# conector_santec.net
KiCad netlist of a schematic drawn in EAGLE
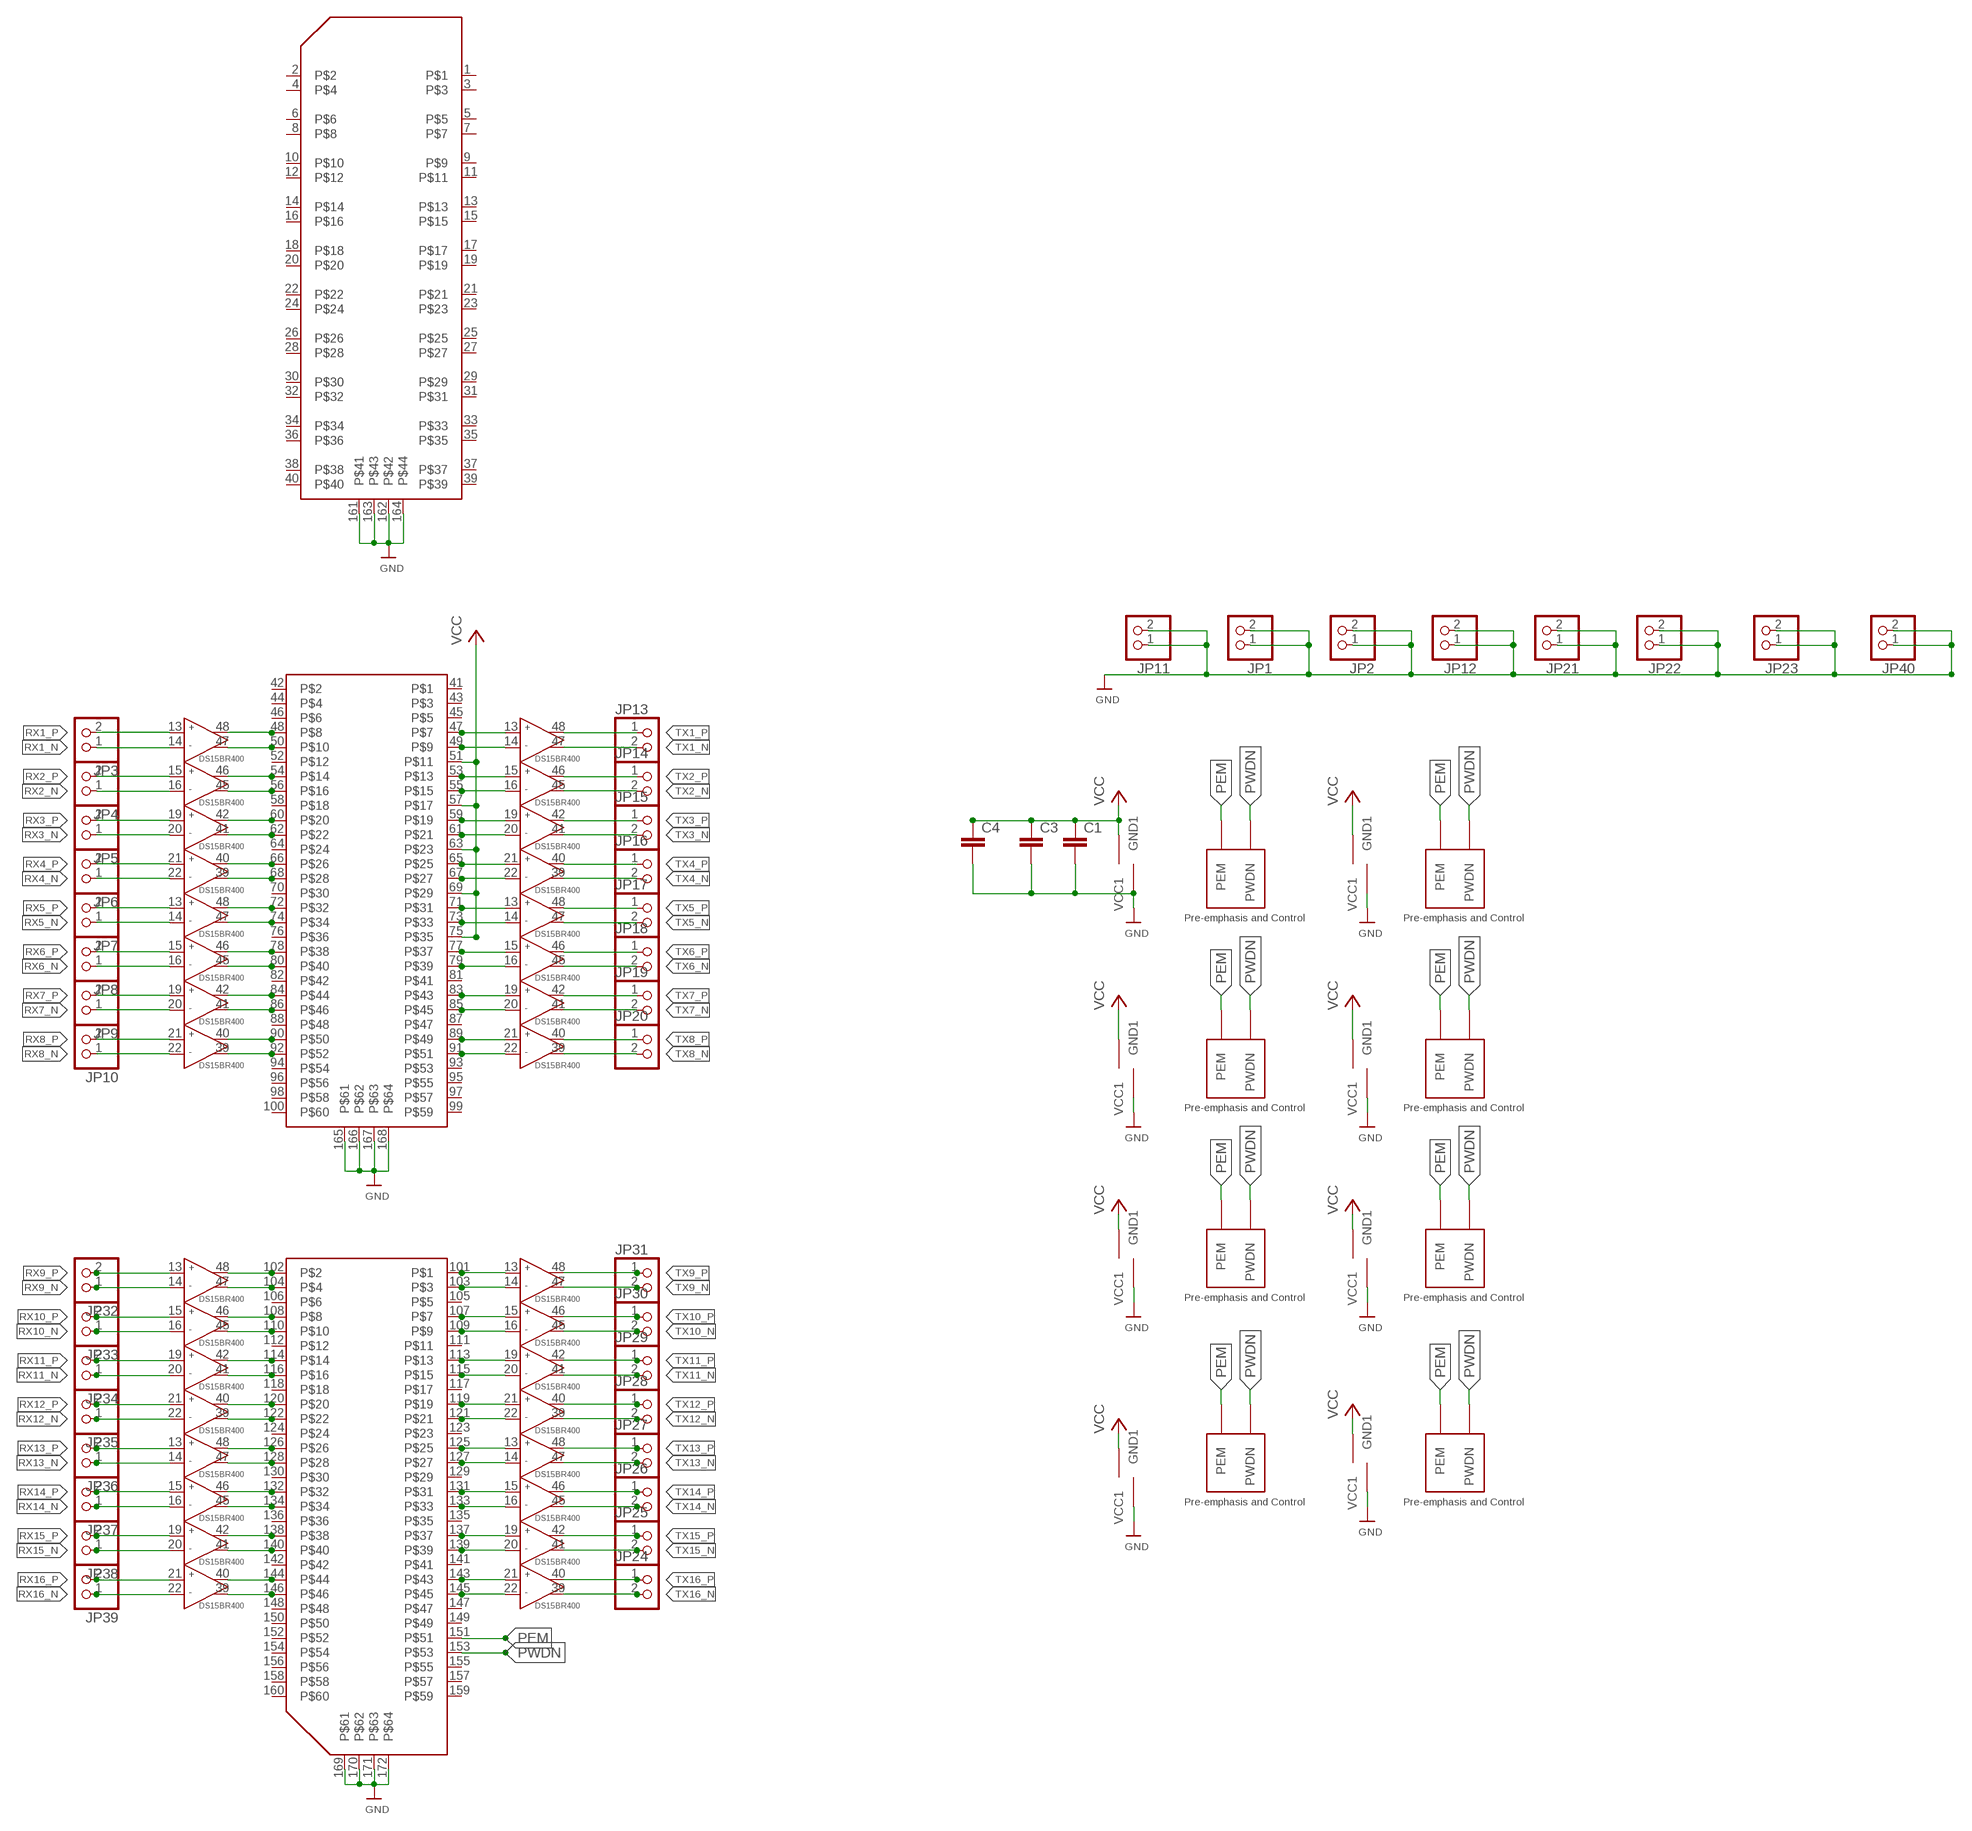
[diagram p0: schematic, sheet 1]

(export (version "E")
  (design (tool "Eeschema 10.0.6"))
  (components
    (comp (ref "C1")
      (value "C-EUC0603")
      (footprint "eagle-import:C0603")
      (libsource (lib "eagle-import") (part "C-EUC0603"))
    )
    (comp (ref "C3")
      (value "C-EUC0603")
      (footprint "eagle-import:C0603")
      (libsource (lib "eagle-import") (part "C-EUC0603"))
    )
    (comp (ref "C4")
      (value "C-EUC0603")
      (footprint "eagle-import:C0603")
      (libsource (lib "eagle-import") (part "C-EUC0603"))
    )
    (comp (ref "JP1")
      (value "HEADER-1X2ROUND")
      (footprint "eagle-import:1X02_ROUND")
      (libsource (lib "eagle-import") (part "HEADER-1X2ROUND"))
    )
    (comp (ref "JP2")
      (value "HEADER-1X2ROUND")
      (footprint "eagle-import:1X02_ROUND")
      (libsource (lib "eagle-import") (part "HEADER-1X2ROUND"))
    )
    (comp (ref "JP3")
      (value "HEADER-1X2ROUND")
      (footprint "eagle-import:1X02_ROUND")
      (libsource (lib "eagle-import") (part "HEADER-1X2ROUND"))
    )
    (comp (ref "JP4")
      (value "HEADER-1X2ROUND")
      (footprint "eagle-import:1X02_ROUND")
      (libsource (lib "eagle-import") (part "HEADER-1X2ROUND"))
    )
    (comp (ref "JP5")
      (value "HEADER-1X2ROUND")
      (footprint "eagle-import:1X02_ROUND")
      (libsource (lib "eagle-import") (part "HEADER-1X2ROUND"))
    )
    (comp (ref "JP6")
      (value "HEADER-1X2ROUND")
      (footprint "eagle-import:1X02_ROUND")
      (libsource (lib "eagle-import") (part "HEADER-1X2ROUND"))
    )
    (comp (ref "JP7")
      (value "HEADER-1X2ROUND")
      (footprint "eagle-import:1X02_ROUND")
      (libsource (lib "eagle-import") (part "HEADER-1X2ROUND"))
    )
    (comp (ref "JP8")
      (value "HEADER-1X2ROUND")
      (footprint "eagle-import:1X02_ROUND")
      (libsource (lib "eagle-import") (part "HEADER-1X2ROUND"))
    )
    (comp (ref "JP9")
      (value "HEADER-1X2ROUND")
      (footprint "eagle-import:1X02_ROUND")
      (libsource (lib "eagle-import") (part "HEADER-1X2ROUND"))
    )
    (comp (ref "JP10")
      (value "HEADER-1X2ROUND")
      (footprint "eagle-import:1X02_ROUND")
      (libsource (lib "eagle-import") (part "HEADER-1X2ROUND"))
    )
    (comp (ref "JP11")
      (value "HEADER-1X2ROUND")
      (footprint "eagle-import:1X02_ROUND")
      (libsource (lib "eagle-import") (part "HEADER-1X2ROUND"))
    )
    (comp (ref "JP12")
      (value "HEADER-1X2ROUND")
      (footprint "eagle-import:1X02_ROUND")
      (libsource (lib "eagle-import") (part "HEADER-1X2ROUND"))
    )
    (comp (ref "JP13")
      (value "HEADER-1X2ROUND")
      (footprint "eagle-import:1X02_ROUND")
      (libsource (lib "eagle-import") (part "HEADER-1X2ROUND"))
    )
    (comp (ref "JP14")
      (value "HEADER-1X2ROUND")
      (footprint "eagle-import:1X02_ROUND")
      (libsource (lib "eagle-import") (part "HEADER-1X2ROUND"))
    )
    (comp (ref "JP15")
      (value "HEADER-1X2ROUND")
      (footprint "eagle-import:1X02_ROUND")
      (libsource (lib "eagle-import") (part "HEADER-1X2ROUND"))
    )
    (comp (ref "JP16")
      (value "HEADER-1X2ROUND")
      (footprint "eagle-import:1X02_ROUND")
      (libsource (lib "eagle-import") (part "HEADER-1X2ROUND"))
    )
    (comp (ref "JP17")
      (value "HEADER-1X2ROUND")
      (footprint "eagle-import:1X02_ROUND")
      (libsource (lib "eagle-import") (part "HEADER-1X2ROUND"))
    )
    (comp (ref "JP18")
      (value "HEADER-1X2ROUND")
      (footprint "eagle-import:1X02_ROUND")
      (libsource (lib "eagle-import") (part "HEADER-1X2ROUND"))
    )
    (comp (ref "JP19")
      (value "HEADER-1X2ROUND")
      (footprint "eagle-import:1X02_ROUND")
      (libsource (lib "eagle-import") (part "HEADER-1X2ROUND"))
    )
    (comp (ref "JP20")
      (value "HEADER-1X2ROUND")
      (footprint "eagle-import:1X02_ROUND")
      (libsource (lib "eagle-import") (part "HEADER-1X2ROUND"))
    )
    (comp (ref "JP21")
      (value "HEADER-1X2ROUND")
      (footprint "eagle-import:1X02_ROUND")
      (libsource (lib "eagle-import") (part "HEADER-1X2ROUND"))
    )
    (comp (ref "JP22")
      (value "HEADER-1X2ROUND")
      (footprint "eagle-import:1X02_ROUND")
      (libsource (lib "eagle-import") (part "HEADER-1X2ROUND"))
    )
    (comp (ref "JP23")
      (value "HEADER-1X2ROUND")
      (footprint "eagle-import:1X02_ROUND")
      (libsource (lib "eagle-import") (part "HEADER-1X2ROUND"))
    )
    (comp (ref "JP24")
      (value "HEADER-1X2ROUND")
      (footprint "eagle-import:1X02_ROUND")
      (libsource (lib "eagle-import") (part "HEADER-1X2ROUND"))
    )
    (comp (ref "JP25")
      (value "HEADER-1X2ROUND")
      (footprint "eagle-import:1X02_ROUND")
      (libsource (lib "eagle-import") (part "HEADER-1X2ROUND"))
    )
    (comp (ref "JP26")
      (value "HEADER-1X2ROUND")
      (footprint "eagle-import:1X02_ROUND")
      (libsource (lib "eagle-import") (part "HEADER-1X2ROUND"))
    )
    (comp (ref "JP27")
      (value "HEADER-1X2ROUND")
      (footprint "eagle-import:1X02_ROUND")
      (libsource (lib "eagle-import") (part "HEADER-1X2ROUND"))
    )
    (comp (ref "JP28")
      (value "HEADER-1X2ROUND")
      (footprint "eagle-import:1X02_ROUND")
      (libsource (lib "eagle-import") (part "HEADER-1X2ROUND"))
    )
    (comp (ref "JP29")
      (value "HEADER-1X2ROUND")
      (footprint "eagle-import:1X02_ROUND")
      (libsource (lib "eagle-import") (part "HEADER-1X2ROUND"))
    )
    (comp (ref "JP30")
      (value "HEADER-1X2ROUND")
      (footprint "eagle-import:1X02_ROUND")
      (libsource (lib "eagle-import") (part "HEADER-1X2ROUND"))
    )
    (comp (ref "JP31")
      (value "HEADER-1X2ROUND")
      (footprint "eagle-import:1X02_ROUND")
      (libsource (lib "eagle-import") (part "HEADER-1X2ROUND"))
    )
    (comp (ref "JP32")
      (value "HEADER-1X2ROUND")
      (footprint "eagle-import:1X02_ROUND")
      (libsource (lib "eagle-import") (part "HEADER-1X2ROUND"))
    )
    (comp (ref "JP33")
      (value "HEADER-1X2ROUND")
      (footprint "eagle-import:1X02_ROUND")
      (libsource (lib "eagle-import") (part "HEADER-1X2ROUND"))
    )
    (comp (ref "JP34")
      (value "HEADER-1X2ROUND")
      (footprint "eagle-import:1X02_ROUND")
      (libsource (lib "eagle-import") (part "HEADER-1X2ROUND"))
    )
    (comp (ref "JP35")
      (value "HEADER-1X2ROUND")
      (footprint "eagle-import:1X02_ROUND")
      (libsource (lib "eagle-import") (part "HEADER-1X2ROUND"))
    )
    (comp (ref "JP36")
      (value "HEADER-1X2ROUND")
      (footprint "eagle-import:1X02_ROUND")
      (libsource (lib "eagle-import") (part "HEADER-1X2ROUND"))
    )
    (comp (ref "JP37")
      (value "HEADER-1X2ROUND")
      (footprint "eagle-import:1X02_ROUND")
      (libsource (lib "eagle-import") (part "HEADER-1X2ROUND"))
    )
    (comp (ref "JP38")
      (value "HEADER-1X2ROUND")
      (footprint "eagle-import:1X02_ROUND")
      (libsource (lib "eagle-import") (part "HEADER-1X2ROUND"))
    )
    (comp (ref "JP39")
      (value "HEADER-1X2ROUND")
      (footprint "eagle-import:1X02_ROUND")
      (libsource (lib "eagle-import") (part "HEADER-1X2ROUND"))
    )
    (comp (ref "JP40")
      (value "HEADER-1X2ROUND")
      (footprint "eagle-import:1X02_ROUND")
      (libsource (lib "eagle-import") (part "HEADER-1X2ROUND"))
    )
    (comp (ref "U$1")
      (value "SAMTEC_ASP-122952-01")
      (footprint "eagle-import:ASP-122952-01")
      (libsource (lib "eagle-import") (part "SAMTEC_ASP-122952-01"))
    )
    (comp (ref "U$4")
      (value "DS15BR400")
      (footprint "eagle-import:TQFP48")
      (libsource (lib "eagle-import") (part "DS15BR400"))
    )
    (comp (ref "U$6")
      (value "DS15BR400")
      (footprint "eagle-import:TQFP48")
      (libsource (lib "eagle-import") (part "DS15BR400"))
    )
    (comp (ref "U$7")
      (value "DS15BR400")
      (footprint "eagle-import:TQFP48")
      (libsource (lib "eagle-import") (part "DS15BR400"))
    )
    (comp (ref "U$8")
      (value "DS15BR400")
      (footprint "eagle-import:TQFP48")
      (libsource (lib "eagle-import") (part "DS15BR400"))
    )
    (comp (ref "U$15")
      (value "DS15BR400")
      (footprint "eagle-import:TQFP48")
      (libsource (lib "eagle-import") (part "DS15BR400"))
    )
    (comp (ref "U$16")
      (value "DS15BR400")
      (footprint "eagle-import:TQFP48")
      (libsource (lib "eagle-import") (part "DS15BR400"))
    )
    (comp (ref "U$17")
      (value "DS15BR400")
      (footprint "eagle-import:TQFP48")
      (libsource (lib "eagle-import") (part "DS15BR400"))
    )
    (comp (ref "U$18")
      (value "DS15BR400")
      (footprint "eagle-import:TQFP48")
      (libsource (lib "eagle-import") (part "DS15BR400"))
    )
  )
  (nets
    (net (code "1") (name "GND") (class "Default")
      (node (ref "C1") (pin "2") (pinfunction "2_2") (pintype "passive"))
      (node (ref "C3") (pin "2") (pinfunction "2_2") (pintype "passive"))
      (node (ref "C4") (pin "2") (pinfunction "2_2") (pintype "passive"))
      (node (ref "JP1") (pin "1") (pinfunction "1_1") (pintype "passive"))
      (node (ref "JP1") (pin "2") (pinfunction "2_2") (pintype "passive"))
      (node (ref "JP11") (pin "1") (pinfunction "1_1") (pintype "passive"))
      (node (ref "JP11") (pin "2") (pinfunction "2_2") (pintype "passive"))
      (node (ref "JP12") (pin "1") (pinfunction "1_1") (pintype "passive"))
      (node (ref "JP12") (pin "2") (pinfunction "2_2") (pintype "passive"))
      (node (ref "JP2") (pin "1") (pinfunction "1_1") (pintype "passive"))
      (node (ref "JP2") (pin "2") (pinfunction "2_2") (pintype "passive"))
      (node (ref "JP21") (pin "1") (pinfunction "1_1") (pintype "passive"))
      (node (ref "JP21") (pin "2") (pinfunction "2_2") (pintype "passive"))
      (node (ref "JP22") (pin "1") (pinfunction "1_1") (pintype "passive"))
      (node (ref "JP22") (pin "2") (pinfunction "2_2") (pintype "passive"))
      (node (ref "JP23") (pin "1") (pinfunction "1_1") (pintype "passive"))
      (node (ref "JP23") (pin "2") (pinfunction "2_2") (pintype "passive"))
      (node (ref "JP40") (pin "1") (pinfunction "1_1") (pintype "passive"))
      (node (ref "JP40") (pin "2") (pinfunction "2_2") (pintype "passive"))
      (node (ref "U$1") (pin "161") (pinfunction "P$41_161") (pintype "bidirectional"))
      (node (ref "U$1") (pin "162") (pinfunction "P$42_162") (pintype "bidirectional"))
      (node (ref "U$1") (pin "163") (pinfunction "P$43_163") (pintype "bidirectional"))
      (node (ref "U$1") (pin "164") (pinfunction "P$44_164") (pintype "bidirectional"))
      (node (ref "U$1") (pin "165") (pinfunction "P$61_165") (pintype "bidirectional"))
      (node (ref "U$1") (pin "166") (pinfunction "P$62_166") (pintype "bidirectional"))
      (node (ref "U$1") (pin "167") (pinfunction "P$63_167") (pintype "bidirectional"))
      (node (ref "U$1") (pin "168") (pinfunction "P$64_168") (pintype "bidirectional"))
      (node (ref "U$1") (pin "169") (pinfunction "P$61_169") (pintype "bidirectional"))
      (node (ref "U$1") (pin "170") (pinfunction "P$62_170") (pintype "bidirectional"))
      (node (ref "U$1") (pin "171") (pinfunction "P$63_171") (pintype "bidirectional"))
      (node (ref "U$1") (pin "172") (pinfunction "P$64_172") (pintype "bidirectional"))
      (node (ref "U$15") (pin "17") (pinfunction "GND1_17") (pintype "bidirectional"))
      (node (ref "U$15") (pin "18") (pinfunction "GND1_18") (pintype "bidirectional"))
      (node (ref "U$15") (pin "23") (pinfunction "GND1_23") (pintype "bidirectional"))
      (node (ref "U$15") (pin "24") (pinfunction "GND1_24") (pintype "bidirectional"))
      (node (ref "U$15") (pin "37") (pinfunction "GND1_37") (pintype "bidirectional"))
      (node (ref "U$15") (pin "38") (pinfunction "GND1_38") (pintype "bidirectional"))
      (node (ref "U$15") (pin "43") (pinfunction "GND1_43") (pintype "bidirectional"))
      (node (ref "U$15") (pin "44") (pinfunction "GND1_44") (pintype "bidirectional"))
      (node (ref "U$15") (pin "8") (pinfunction "GND1_8") (pintype "bidirectional"))
      (node (ref "U$15") (pin "9") (pinfunction "GND1_9") (pintype "bidirectional"))
      (node (ref "U$16") (pin "17") (pinfunction "GND1_17") (pintype "bidirectional"))
      (node (ref "U$16") (pin "18") (pinfunction "GND1_18") (pintype "bidirectional"))
      (node (ref "U$16") (pin "23") (pinfunction "GND1_23") (pintype "bidirectional"))
      (node (ref "U$16") (pin "24") (pinfunction "GND1_24") (pintype "bidirectional"))
      (node (ref "U$16") (pin "37") (pinfunction "GND1_37") (pintype "bidirectional"))
      (node (ref "U$16") (pin "38") (pinfunction "GND1_38") (pintype "bidirectional"))
      (node (ref "U$16") (pin "43") (pinfunction "GND1_43") (pintype "bidirectional"))
      (node (ref "U$16") (pin "44") (pinfunction "GND1_44") (pintype "bidirectional"))
      (node (ref "U$16") (pin "8") (pinfunction "GND1_8") (pintype "bidirectional"))
      (node (ref "U$16") (pin "9") (pinfunction "GND1_9") (pintype "bidirectional"))
      (node (ref "U$17") (pin "17") (pinfunction "GND1_17") (pintype "bidirectional"))
      (node (ref "U$17") (pin "18") (pinfunction "GND1_18") (pintype "bidirectional"))
      (node (ref "U$17") (pin "23") (pinfunction "GND1_23") (pintype "bidirectional"))
      (node (ref "U$17") (pin "24") (pinfunction "GND1_24") (pintype "bidirectional"))
      (node (ref "U$17") (pin "37") (pinfunction "GND1_37") (pintype "bidirectional"))
      (node (ref "U$17") (pin "38") (pinfunction "GND1_38") (pintype "bidirectional"))
      (node (ref "U$17") (pin "43") (pinfunction "GND1_43") (pintype "bidirectional"))
      (node (ref "U$17") (pin "44") (pinfunction "GND1_44") (pintype "bidirectional"))
      (node (ref "U$17") (pin "8") (pinfunction "GND1_8") (pintype "bidirectional"))
      (node (ref "U$17") (pin "9") (pinfunction "GND1_9") (pintype "bidirectional"))
      (node (ref "U$18") (pin "17") (pinfunction "GND1_17") (pintype "bidirectional"))
      (node (ref "U$18") (pin "18") (pinfunction "GND1_18") (pintype "bidirectional"))
      (node (ref "U$18") (pin "23") (pinfunction "GND1_23") (pintype "bidirectional"))
      (node (ref "U$18") (pin "24") (pinfunction "GND1_24") (pintype "bidirectional"))
      (node (ref "U$18") (pin "37") (pinfunction "GND1_37") (pintype "bidirectional"))
      (node (ref "U$18") (pin "38") (pinfunction "GND1_38") (pintype "bidirectional"))
      (node (ref "U$18") (pin "43") (pinfunction "GND1_43") (pintype "bidirectional"))
      (node (ref "U$18") (pin "44") (pinfunction "GND1_44") (pintype "bidirectional"))
      (node (ref "U$18") (pin "8") (pinfunction "GND1_8") (pintype "bidirectional"))
      (node (ref "U$18") (pin "9") (pinfunction "GND1_9") (pintype "bidirectional"))
      (node (ref "U$4") (pin "17") (pinfunction "GND1_17") (pintype "bidirectional"))
      (node (ref "U$4") (pin "18") (pinfunction "GND1_18") (pintype "bidirectional"))
      (node (ref "U$4") (pin "23") (pinfunction "GND1_23") (pintype "bidirectional"))
      (node (ref "U$4") (pin "24") (pinfunction "GND1_24") (pintype "bidirectional"))
      (node (ref "U$4") (pin "37") (pinfunction "GND1_37") (pintype "bidirectional"))
      (node (ref "U$4") (pin "38") (pinfunction "GND1_38") (pintype "bidirectional"))
      (node (ref "U$4") (pin "43") (pinfunction "GND1_43") (pintype "bidirectional"))
      (node (ref "U$4") (pin "44") (pinfunction "GND1_44") (pintype "bidirectional"))
      (node (ref "U$4") (pin "8") (pinfunction "GND1_8") (pintype "bidirectional"))
      (node (ref "U$4") (pin "9") (pinfunction "GND1_9") (pintype "bidirectional"))
      (node (ref "U$6") (pin "17") (pinfunction "GND1_17") (pintype "bidirectional"))
      (node (ref "U$6") (pin "18") (pinfunction "GND1_18") (pintype "bidirectional"))
      (node (ref "U$6") (pin "23") (pinfunction "GND1_23") (pintype "bidirectional"))
      (node (ref "U$6") (pin "24") (pinfunction "GND1_24") (pintype "bidirectional"))
      (node (ref "U$6") (pin "37") (pinfunction "GND1_37") (pintype "bidirectional"))
      (node (ref "U$6") (pin "38") (pinfunction "GND1_38") (pintype "bidirectional"))
      (node (ref "U$6") (pin "43") (pinfunction "GND1_43") (pintype "bidirectional"))
      (node (ref "U$6") (pin "44") (pinfunction "GND1_44") (pintype "bidirectional"))
      (node (ref "U$6") (pin "8") (pinfunction "GND1_8") (pintype "bidirectional"))
      (node (ref "U$6") (pin "9") (pinfunction "GND1_9") (pintype "bidirectional"))
      (node (ref "U$7") (pin "17") (pinfunction "GND1_17") (pintype "bidirectional"))
      (node (ref "U$7") (pin "18") (pinfunction "GND1_18") (pintype "bidirectional"))
      (node (ref "U$7") (pin "23") (pinfunction "GND1_23") (pintype "bidirectional"))
      (node (ref "U$7") (pin "24") (pinfunction "GND1_24") (pintype "bidirectional"))
      (node (ref "U$7") (pin "37") (pinfunction "GND1_37") (pintype "bidirectional"))
      (node (ref "U$7") (pin "38") (pinfunction "GND1_38") (pintype "bidirectional"))
      (node (ref "U$7") (pin "43") (pinfunction "GND1_43") (pintype "bidirectional"))
      (node (ref "U$7") (pin "44") (pinfunction "GND1_44") (pintype "bidirectional"))
      (node (ref "U$7") (pin "8") (pinfunction "GND1_8") (pintype "bidirectional"))
      (node (ref "U$7") (pin "9") (pinfunction "GND1_9") (pintype "bidirectional"))
      (node (ref "U$8") (pin "17") (pinfunction "GND1_17") (pintype "bidirectional"))
      (node (ref "U$8") (pin "18") (pinfunction "GND1_18") (pintype "bidirectional"))
      (node (ref "U$8") (pin "23") (pinfunction "GND1_23") (pintype "bidirectional"))
      (node (ref "U$8") (pin "24") (pinfunction "GND1_24") (pintype "bidirectional"))
      (node (ref "U$8") (pin "37") (pinfunction "GND1_37") (pintype "bidirectional"))
      (node (ref "U$8") (pin "38") (pinfunction "GND1_38") (pintype "bidirectional"))
      (node (ref "U$8") (pin "43") (pinfunction "GND1_43") (pintype "bidirectional"))
      (node (ref "U$8") (pin "44") (pinfunction "GND1_44") (pintype "bidirectional"))
      (node (ref "U$8") (pin "8") (pinfunction "GND1_8") (pintype "bidirectional"))
      (node (ref "U$8") (pin "9") (pinfunction "GND1_9") (pintype "bidirectional"))
    )
    (net (code "2") (name "Net-(U$1B-P$7)") (class "Default")
      (node (ref "U$1") (pin "47") (pinfunction "P$7_47") (pintype "bidirectional"))
      (node (ref "U$4") (pin "13") (pinfunction "IN+_13") (pintype "input"))
    )
    (net (code "3") (name "Net-(U$1B-P$8)") (class "Default")
      (node (ref "U$1") (pin "48") (pinfunction "P$8_48") (pintype "bidirectional"))
      (node (ref "U$7") (pin "48") (pinfunction "OUT+_48") (pintype "output"))
    )
    (net (code "4") (name "Net-(U$1B-P$9)") (class "Default")
      (node (ref "U$1") (pin "49") (pinfunction "P$9_49") (pintype "bidirectional"))
      (node (ref "U$4") (pin "14") (pinfunction "IN-_14") (pintype "input"))
    )
    (net (code "5") (name "Net-(U$1B-P$10)") (class "Default")
      (node (ref "U$1") (pin "50") (pinfunction "P$10_50") (pintype "bidirectional"))
      (node (ref "U$7") (pin "47") (pinfunction "OUT-_47") (pintype "output"))
    )
    (net (code "6") (name "Net-(U$1B-P$13)") (class "Default")
      (node (ref "U$1") (pin "53") (pinfunction "P$13_53") (pintype "bidirectional"))
      (node (ref "U$4") (pin "15") (pinfunction "IN+_15") (pintype "input"))
    )
    (net (code "7") (name "Net-(U$1B-P$14)") (class "Default")
      (node (ref "U$1") (pin "54") (pinfunction "P$14_54") (pintype "bidirectional"))
      (node (ref "U$7") (pin "46") (pinfunction "OUT+_46") (pintype "output"))
    )
    (net (code "8") (name "Net-(U$1B-P$15)") (class "Default")
      (node (ref "U$1") (pin "55") (pinfunction "P$15_55") (pintype "bidirectional"))
      (node (ref "U$4") (pin "16") (pinfunction "IN-_16") (pintype "input"))
    )
    (net (code "9") (name "Net-(U$1B-P$16)") (class "Default")
      (node (ref "U$1") (pin "56") (pinfunction "P$16_56") (pintype "bidirectional"))
      (node (ref "U$7") (pin "45") (pinfunction "OUT-_45") (pintype "output"))
    )
    (net (code "10") (name "Net-(U$1B-P$19)") (class "Default")
      (node (ref "U$1") (pin "59") (pinfunction "P$19_59") (pintype "bidirectional"))
      (node (ref "U$4") (pin "19") (pinfunction "IN+_19") (pintype "input"))
    )
    (net (code "11") (name "Net-(U$1B-P$20)") (class "Default")
      (node (ref "U$1") (pin "60") (pinfunction "P$20_60") (pintype "bidirectional"))
      (node (ref "U$7") (pin "42") (pinfunction "OUT+_42") (pintype "output"))
    )
    (net (code "12") (name "Net-(U$1B-P$21)") (class "Default")
      (node (ref "U$1") (pin "61") (pinfunction "P$21_61") (pintype "bidirectional"))
      (node (ref "U$4") (pin "20") (pinfunction "IN-_20") (pintype "input"))
    )
    (net (code "13") (name "Net-(U$1B-P$22)") (class "Default")
      (node (ref "U$1") (pin "62") (pinfunction "P$22_62") (pintype "bidirectional"))
      (node (ref "U$7") (pin "41") (pinfunction "OUT-_41") (pintype "output"))
    )
    (net (code "14") (name "Net-(U$1B-P$25)") (class "Default")
      (node (ref "U$1") (pin "65") (pinfunction "P$25_65") (pintype "bidirectional"))
      (node (ref "U$4") (pin "21") (pinfunction "IN+_21") (pintype "input"))
    )
    (net (code "15") (name "Net-(U$1B-P$26)") (class "Default")
      (node (ref "U$1") (pin "66") (pinfunction "P$26_66") (pintype "bidirectional"))
      (node (ref "U$7") (pin "40") (pinfunction "OUT+_40") (pintype "output"))
    )
    (net (code "16") (name "Net-(U$1B-P$27)") (class "Default")
      (node (ref "U$1") (pin "67") (pinfunction "P$27_67") (pintype "bidirectional"))
      (node (ref "U$4") (pin "22") (pinfunction "IN-_22") (pintype "input"))
    )
    (net (code "17") (name "Net-(U$1B-P$28)") (class "Default")
      (node (ref "U$1") (pin "68") (pinfunction "P$28_68") (pintype "bidirectional"))
      (node (ref "U$7") (pin "39") (pinfunction "OUT-_39") (pintype "output"))
    )
    (net (code "18") (name "Net-(U$1B-P$31)") (class "Default")
      (node (ref "U$1") (pin "71") (pinfunction "P$31_71") (pintype "bidirectional"))
      (node (ref "U$6") (pin "13") (pinfunction "IN+_13") (pintype "input"))
    )
    (net (code "19") (name "Net-(U$1B-P$32)") (class "Default")
      (node (ref "U$1") (pin "72") (pinfunction "P$32_72") (pintype "bidirectional"))
      (node (ref "U$8") (pin "48") (pinfunction "OUT+_48") (pintype "output"))
    )
    (net (code "20") (name "Net-(U$1B-P$33)") (class "Default")
      (node (ref "U$1") (pin "73") (pinfunction "P$33_73") (pintype "bidirectional"))
      (node (ref "U$6") (pin "14") (pinfunction "IN-_14") (pintype "input"))
    )
    (net (code "21") (name "Net-(U$1B-P$34)") (class "Default")
      (node (ref "U$1") (pin "74") (pinfunction "P$34_74") (pintype "bidirectional"))
      (node (ref "U$8") (pin "47") (pinfunction "OUT-_47") (pintype "output"))
    )
    (net (code "22") (name "Net-(U$1B-P$37)") (class "Default")
      (node (ref "U$1") (pin "77") (pinfunction "P$37_77") (pintype "bidirectional"))
      (node (ref "U$6") (pin "15") (pinfunction "IN+_15") (pintype "input"))
    )
    (net (code "23") (name "Net-(U$1B-P$38)") (class "Default")
      (node (ref "U$1") (pin "78") (pinfunction "P$38_78") (pintype "bidirectional"))
      (node (ref "U$8") (pin "46") (pinfunction "OUT+_46") (pintype "output"))
    )
    (net (code "24") (name "Net-(U$1B-P$39)") (class "Default")
      (node (ref "U$1") (pin "79") (pinfunction "P$39_79") (pintype "bidirectional"))
      (node (ref "U$6") (pin "16") (pinfunction "IN-_16") (pintype "input"))
    )
    (net (code "25") (name "Net-(U$1B-P$40)") (class "Default")
      (node (ref "U$1") (pin "80") (pinfunction "P$40_80") (pintype "bidirectional"))
      (node (ref "U$8") (pin "45") (pinfunction "OUT-_45") (pintype "output"))
    )
    (net (code "26") (name "Net-(U$1B-P$43)") (class "Default")
      (node (ref "U$1") (pin "83") (pinfunction "P$43_83") (pintype "bidirectional"))
      (node (ref "U$6") (pin "19") (pinfunction "IN+_19") (pintype "input"))
    )
    (net (code "27") (name "Net-(U$1B-P$44)") (class "Default")
      (node (ref "U$1") (pin "84") (pinfunction "P$44_84") (pintype "bidirectional"))
      (node (ref "U$8") (pin "42") (pinfunction "OUT+_42") (pintype "output"))
    )
    (net (code "28") (name "Net-(U$1B-P$45)") (class "Default")
      (node (ref "U$1") (pin "85") (pinfunction "P$45_85") (pintype "bidirectional"))
      (node (ref "U$6") (pin "20") (pinfunction "IN-_20") (pintype "input"))
    )
    (net (code "29") (name "Net-(U$1B-P$46)") (class "Default")
      (node (ref "U$1") (pin "86") (pinfunction "P$46_86") (pintype "bidirectional"))
      (node (ref "U$8") (pin "41") (pinfunction "OUT-_41") (pintype "output"))
    )
    (net (code "30") (name "Net-(U$1B-P$49)") (class "Default")
      (node (ref "U$1") (pin "89") (pinfunction "P$49_89") (pintype "bidirectional"))
      (node (ref "U$6") (pin "21") (pinfunction "IN+_21") (pintype "input"))
    )
    (net (code "31") (name "Net-(U$1B-P$50)") (class "Default")
      (node (ref "U$1") (pin "90") (pinfunction "P$50_90") (pintype "bidirectional"))
      (node (ref "U$8") (pin "40") (pinfunction "OUT+_40") (pintype "output"))
    )
    (net (code "32") (name "Net-(U$1B-P$51)") (class "Default")
      (node (ref "U$1") (pin "91") (pinfunction "P$51_91") (pintype "bidirectional"))
      (node (ref "U$6") (pin "22") (pinfunction "IN-_22") (pintype "input"))
    )
    (net (code "33") (name "Net-(U$1B-P$52)") (class "Default")
      (node (ref "U$1") (pin "92") (pinfunction "P$52_92") (pintype "bidirectional"))
      (node (ref "U$8") (pin "39") (pinfunction "OUT-_39") (pintype "output"))
    )
    (net (code "34") (name "Net-(U$15A-IN+)") (class "Default")
      (node (ref "U$1") (pin "101") (pinfunction "P$1_101") (pintype "bidirectional"))
      (node (ref "U$15") (pin "13") (pinfunction "IN+_13") (pintype "input"))
    )
    (net (code "35") (name "Net-(U$15A-IN-)") (class "Default")
      (node (ref "U$1") (pin "103") (pinfunction "P$3_103") (pintype "bidirectional"))
      (node (ref "U$15") (pin "14") (pinfunction "IN-_14") (pintype "input"))
    )
    (net (code "36") (name "Net-(U$15B-IN+)") (class "Default")
      (node (ref "U$1") (pin "107") (pinfunction "P$7_107") (pintype "bidirectional"))
      (node (ref "U$15") (pin "15") (pinfunction "IN+_15") (pintype "input"))
    )
    (net (code "37") (name "Net-(U$15B-IN-)") (class "Default")
      (node (ref "U$1") (pin "109") (pinfunction "P$9_109") (pintype "bidirectional"))
      (node (ref "U$15") (pin "16") (pinfunction "IN-_16") (pintype "input"))
    )
    (net (code "38") (name "Net-(U$15C-IN+)") (class "Default")
      (node (ref "U$1") (pin "113") (pinfunction "P$13_113") (pintype "bidirectional"))
      (node (ref "U$15") (pin "19") (pinfunction "IN+_19") (pintype "input"))
    )
    (net (code "39") (name "Net-(U$15C-IN-)") (class "Default")
      (node (ref "U$1") (pin "115") (pinfunction "P$15_115") (pintype "bidirectional"))
      (node (ref "U$15") (pin "20") (pinfunction "IN-_20") (pintype "input"))
    )
    (net (code "40") (name "Net-(U$15D-IN+)") (class "Default")
      (node (ref "U$1") (pin "119") (pinfunction "P$19_119") (pintype "bidirectional"))
      (node (ref "U$15") (pin "21") (pinfunction "IN+_21") (pintype "input"))
    )
    (net (code "41") (name "Net-(U$15D-IN-)") (class "Default")
      (node (ref "U$1") (pin "121") (pinfunction "P$21_121") (pintype "bidirectional"))
      (node (ref "U$15") (pin "22") (pinfunction "IN-_22") (pintype "input"))
    )
    (net (code "42") (name "Net-(U$16A-IN+)") (class "Default")
      (node (ref "U$1") (pin "125") (pinfunction "P$25_125") (pintype "bidirectional"))
      (node (ref "U$16") (pin "13") (pinfunction "IN+_13") (pintype "input"))
    )
    (net (code "43") (name "Net-(U$16A-IN-)") (class "Default")
      (node (ref "U$1") (pin "127") (pinfunction "P$27_127") (pintype "bidirectional"))
      (node (ref "U$16") (pin "14") (pinfunction "IN-_14") (pintype "input"))
    )
    (net (code "44") (name "Net-(U$16B-IN+)") (class "Default")
      (node (ref "U$1") (pin "131") (pinfunction "P$31_131") (pintype "bidirectional"))
      (node (ref "U$16") (pin "15") (pinfunction "IN+_15") (pintype "input"))
    )
    (net (code "45") (name "Net-(U$16B-IN-)") (class "Default")
      (node (ref "U$1") (pin "133") (pinfunction "P$33_133") (pintype "bidirectional"))
      (node (ref "U$16") (pin "16") (pinfunction "IN-_16") (pintype "input"))
    )
    (net (code "46") (name "Net-(U$16C-IN+)") (class "Default")
      (node (ref "U$1") (pin "137") (pinfunction "P$37_137") (pintype "bidirectional"))
      (node (ref "U$16") (pin "19") (pinfunction "IN+_19") (pintype "input"))
    )
    (net (code "47") (name "Net-(U$16C-IN-)") (class "Default")
      (node (ref "U$1") (pin "139") (pinfunction "P$39_139") (pintype "bidirectional"))
      (node (ref "U$16") (pin "20") (pinfunction "IN-_20") (pintype "input"))
    )
    (net (code "48") (name "Net-(U$16D-IN+)") (class "Default")
      (node (ref "U$1") (pin "143") (pinfunction "P$43_143") (pintype "bidirectional"))
      (node (ref "U$16") (pin "21") (pinfunction "IN+_21") (pintype "input"))
    )
    (net (code "49") (name "Net-(U$16D-IN-)") (class "Default")
      (node (ref "U$1") (pin "145") (pinfunction "P$45_145") (pintype "bidirectional"))
      (node (ref "U$16") (pin "22") (pinfunction "IN-_22") (pintype "input"))
    )
    (net (code "50") (name "Net-(U$17A-OUT+)") (class "Default")
      (node (ref "U$1") (pin "102") (pinfunction "P$2_102") (pintype "bidirectional"))
      (node (ref "U$17") (pin "48") (pinfunction "OUT+_48") (pintype "output"))
    )
    (net (code "51") (name "Net-(U$17A-OUT-)") (class "Default")
      (node (ref "U$1") (pin "104") (pinfunction "P$4_104") (pintype "bidirectional"))
      (node (ref "U$17") (pin "47") (pinfunction "OUT-_47") (pintype "output"))
    )
    (net (code "52") (name "Net-(U$17B-OUT+)") (class "Default")
      (node (ref "U$1") (pin "108") (pinfunction "P$8_108") (pintype "bidirectional"))
      (node (ref "U$17") (pin "46") (pinfunction "OUT+_46") (pintype "output"))
    )
    (net (code "53") (name "Net-(U$17B-OUT-)") (class "Default")
      (node (ref "U$1") (pin "110") (pinfunction "P$10_110") (pintype "bidirectional"))
      (node (ref "U$17") (pin "45") (pinfunction "OUT-_45") (pintype "output"))
    )
    (net (code "54") (name "Net-(U$17C-OUT+)") (class "Default")
      (node (ref "U$1") (pin "114") (pinfunction "P$14_114") (pintype "bidirectional"))
      (node (ref "U$17") (pin "42") (pinfunction "OUT+_42") (pintype "output"))
    )
    (net (code "55") (name "Net-(U$17C-OUT-)") (class "Default")
      (node (ref "U$1") (pin "116") (pinfunction "P$16_116") (pintype "bidirectional"))
      (node (ref "U$17") (pin "41") (pinfunction "OUT-_41") (pintype "output"))
    )
    (net (code "56") (name "Net-(U$17D-OUT+)") (class "Default")
      (node (ref "U$1") (pin "120") (pinfunction "P$20_120") (pintype "bidirectional"))
      (node (ref "U$17") (pin "40") (pinfunction "OUT+_40") (pintype "output"))
    )
    (net (code "57") (name "Net-(U$17D-OUT-)") (class "Default")
      (node (ref "U$1") (pin "122") (pinfunction "P$22_122") (pintype "bidirectional"))
      (node (ref "U$17") (pin "39") (pinfunction "OUT-_39") (pintype "output"))
    )
    (net (code "58") (name "Net-(U$18A-OUT+)") (class "Default")
      (node (ref "U$1") (pin "126") (pinfunction "P$26_126") (pintype "bidirectional"))
      (node (ref "U$18") (pin "48") (pinfunction "OUT+_48") (pintype "output"))
    )
    (net (code "59") (name "Net-(U$18A-OUT-)") (class "Default")
      (node (ref "U$1") (pin "128") (pinfunction "P$28_128") (pintype "bidirectional"))
      (node (ref "U$18") (pin "47") (pinfunction "OUT-_47") (pintype "output"))
    )
    (net (code "60") (name "Net-(U$18B-OUT+)") (class "Default")
      (node (ref "U$1") (pin "132") (pinfunction "P$32_132") (pintype "bidirectional"))
      (node (ref "U$18") (pin "46") (pinfunction "OUT+_46") (pintype "output"))
    )
    (net (code "61") (name "Net-(U$18B-OUT-)") (class "Default")
      (node (ref "U$1") (pin "134") (pinfunction "P$34_134") (pintype "bidirectional"))
      (node (ref "U$18") (pin "45") (pinfunction "OUT-_45") (pintype "output"))
    )
    (net (code "62") (name "Net-(U$18C-OUT+)") (class "Default")
      (node (ref "U$1") (pin "138") (pinfunction "P$38_138") (pintype "bidirectional"))
      (node (ref "U$18") (pin "42") (pinfunction "OUT+_42") (pintype "output"))
    )
    (net (code "63") (name "Net-(U$18C-OUT-)") (class "Default")
      (node (ref "U$1") (pin "140") (pinfunction "P$40_140") (pintype "bidirectional"))
      (node (ref "U$18") (pin "41") (pinfunction "OUT-_41") (pintype "output"))
    )
    (net (code "64") (name "Net-(U$18D-OUT+)") (class "Default")
      (node (ref "U$1") (pin "144") (pinfunction "P$44_144") (pintype "bidirectional"))
      (node (ref "U$18") (pin "40") (pinfunction "OUT+_40") (pintype "output"))
    )
    (net (code "65") (name "Net-(U$18D-OUT-)") (class "Default")
      (node (ref "U$1") (pin "146") (pinfunction "P$46_146") (pintype "bidirectional"))
      (node (ref "U$18") (pin "39") (pinfunction "OUT-_39") (pintype "output"))
    )
    (net (code "66") (name "PEM") (class "Default")
      (node (ref "U$1") (pin "151") (pinfunction "P$51_151") (pintype "bidirectional"))
      (node (ref "U$15") (pin "2") (pinfunction "PEM_2") (pintype "bidirectional"))
      (node (ref "U$16") (pin "2") (pinfunction "PEM_2") (pintype "bidirectional"))
      (node (ref "U$17") (pin "2") (pinfunction "PEM_2") (pintype "bidirectional"))
      (node (ref "U$18") (pin "2") (pinfunction "PEM_2") (pintype "bidirectional"))
      (node (ref "U$4") (pin "2") (pinfunction "PEM_2") (pintype "bidirectional"))
      (node (ref "U$6") (pin "2") (pinfunction "PEM_2") (pintype "bidirectional"))
      (node (ref "U$7") (pin "2") (pinfunction "PEM_2") (pintype "bidirectional"))
      (node (ref "U$8") (pin "2") (pinfunction "PEM_2") (pintype "bidirectional"))
    )
    (net (code "67") (name "PWDN") (class "Default")
      (node (ref "U$1") (pin "153") (pinfunction "P$53_153") (pintype "bidirectional"))
      (node (ref "U$15") (pin "12") (pinfunction "PWDN_12") (pintype "bidirectional"))
      (node (ref "U$16") (pin "12") (pinfunction "PWDN_12") (pintype "bidirectional"))
      (node (ref "U$17") (pin "12") (pinfunction "PWDN_12") (pintype "bidirectional"))
      (node (ref "U$18") (pin "12") (pinfunction "PWDN_12") (pintype "bidirectional"))
      (node (ref "U$4") (pin "12") (pinfunction "PWDN_12") (pintype "bidirectional"))
      (node (ref "U$6") (pin "12") (pinfunction "PWDN_12") (pintype "bidirectional"))
      (node (ref "U$7") (pin "12") (pinfunction "PWDN_12") (pintype "bidirectional"))
      (node (ref "U$8") (pin "12") (pinfunction "PWDN_12") (pintype "bidirectional"))
    )
    (net (code "68") (name "RX1_N") (class "Default")
      (node (ref "JP3") (pin "1") (pinfunction "1_1") (pintype "passive"))
      (node (ref "U$7") (pin "14") (pinfunction "IN-_14") (pintype "input"))
    )
    (net (code "69") (name "RX1_P") (class "Default")
      (node (ref "JP3") (pin "2") (pinfunction "2_2") (pintype "passive"))
      (node (ref "U$7") (pin "13") (pinfunction "IN+_13") (pintype "input"))
    )
    (net (code "70") (name "RX2_N") (class "Default")
      (node (ref "JP4") (pin "1") (pinfunction "1_1") (pintype "passive"))
      (node (ref "U$7") (pin "16") (pinfunction "IN-_16") (pintype "input"))
    )
    (net (code "71") (name "RX2_P") (class "Default")
      (node (ref "JP4") (pin "2") (pinfunction "2_2") (pintype "passive"))
      (node (ref "U$7") (pin "15") (pinfunction "IN+_15") (pintype "input"))
    )
    (net (code "72") (name "RX3_N") (class "Default")
      (node (ref "JP5") (pin "1") (pinfunction "1_1") (pintype "passive"))
      (node (ref "U$7") (pin "20") (pinfunction "IN-_20") (pintype "input"))
    )
    (net (code "73") (name "RX3_P") (class "Default")
      (node (ref "JP5") (pin "2") (pinfunction "2_2") (pintype "passive"))
      (node (ref "U$7") (pin "19") (pinfunction "IN+_19") (pintype "input"))
    )
    (net (code "74") (name "RX4_N") (class "Default")
      (node (ref "JP6") (pin "1") (pinfunction "1_1") (pintype "passive"))
      (node (ref "U$7") (pin "22") (pinfunction "IN-_22") (pintype "input"))
    )
    (net (code "75") (name "RX4_P") (class "Default")
      (node (ref "JP6") (pin "2") (pinfunction "2_2") (pintype "passive"))
      (node (ref "U$7") (pin "21") (pinfunction "IN+_21") (pintype "input"))
    )
    (net (code "76") (name "RX5_N") (class "Default")
      (node (ref "JP7") (pin "1") (pinfunction "1_1") (pintype "passive"))
      (node (ref "U$8") (pin "14") (pinfunction "IN-_14") (pintype "input"))
    )
    (net (code "77") (name "RX5_P") (class "Default")
      (node (ref "JP7") (pin "2") (pinfunction "2_2") (pintype "passive"))
      (node (ref "U$8") (pin "13") (pinfunction "IN+_13") (pintype "input"))
    )
    (net (code "78") (name "RX6_N") (class "Default")
      (node (ref "JP8") (pin "1") (pinfunction "1_1") (pintype "passive"))
      (node (ref "U$8") (pin "16") (pinfunction "IN-_16") (pintype "input"))
    )
    (net (code "79") (name "RX6_P") (class "Default")
      (node (ref "JP8") (pin "2") (pinfunction "2_2") (pintype "passive"))
      (node (ref "U$8") (pin "15") (pinfunction "IN+_15") (pintype "input"))
    )
    (net (code "80") (name "RX7_N") (class "Default")
      (node (ref "JP9") (pin "1") (pinfunction "1_1") (pintype "passive"))
      (node (ref "U$8") (pin "20") (pinfunction "IN-_20") (pintype "input"))
    )
    (net (code "81") (name "RX7_P") (class "Default")
      (node (ref "JP9") (pin "2") (pinfunction "2_2") (pintype "passive"))
      (node (ref "U$8") (pin "19") (pinfunction "IN+_19") (pintype "input"))
    )
    (net (code "82") (name "RX8_N") (class "Default")
      (node (ref "JP10") (pin "1") (pinfunction "1_1") (pintype "passive"))
      (node (ref "U$8") (pin "22") (pinfunction "IN-_22") (pintype "input"))
    )
    (net (code "83") (name "RX8_P") (class "Default")
      (node (ref "JP10") (pin "2") (pinfunction "2_2") (pintype "passive"))
      (node (ref "U$8") (pin "21") (pinfunction "IN+_21") (pintype "input"))
    )
    (net (code "84") (name "RX9_N") (class "Default")
      (node (ref "JP32") (pin "1") (pinfunction "1_1") (pintype "passive"))
      (node (ref "U$17") (pin "14") (pinfunction "IN-_14") (pintype "input"))
    )
    (net (code "85") (name "RX9_P") (class "Default")
      (node (ref "JP32") (pin "2") (pinfunction "2_2") (pintype "passive"))
      (node (ref "U$17") (pin "13") (pinfunction "IN+_13") (pintype "input"))
    )
    (net (code "86") (name "RX10_N") (class "Default")
      (node (ref "JP33") (pin "1") (pinfunction "1_1") (pintype "passive"))
      (node (ref "U$17") (pin "16") (pinfunction "IN-_16") (pintype "input"))
    )
    (net (code "87") (name "RX10_P") (class "Default")
      (node (ref "JP33") (pin "2") (pinfunction "2_2") (pintype "passive"))
      (node (ref "U$17") (pin "15") (pinfunction "IN+_15") (pintype "input"))
    )
    (net (code "88") (name "RX11_N") (class "Default")
      (node (ref "JP34") (pin "1") (pinfunction "1_1") (pintype "passive"))
      (node (ref "U$17") (pin "20") (pinfunction "IN-_20") (pintype "input"))
    )
    (net (code "89") (name "RX11_P") (class "Default")
      (node (ref "JP34") (pin "2") (pinfunction "2_2") (pintype "passive"))
      (node (ref "U$17") (pin "19") (pinfunction "IN+_19") (pintype "input"))
    )
    (net (code "90") (name "RX12_N") (class "Default")
      (node (ref "JP35") (pin "1") (pinfunction "1_1") (pintype "passive"))
      (node (ref "U$17") (pin "22") (pinfunction "IN-_22") (pintype "input"))
    )
    (net (code "91") (name "RX12_P") (class "Default")
      (node (ref "JP35") (pin "2") (pinfunction "2_2") (pintype "passive"))
      (node (ref "U$17") (pin "21") (pinfunction "IN+_21") (pintype "input"))
    )
    (net (code "92") (name "RX13_N") (class "Default")
      (node (ref "JP36") (pin "1") (pinfunction "1_1") (pintype "passive"))
      (node (ref "U$18") (pin "14") (pinfunction "IN-_14") (pintype "input"))
    )
    (net (code "93") (name "RX13_P") (class "Default")
      (node (ref "JP36") (pin "2") (pinfunction "2_2") (pintype "passive"))
      (node (ref "U$18") (pin "13") (pinfunction "IN+_13") (pintype "input"))
    )
    (net (code "94") (name "RX14_N") (class "Default")
      (node (ref "JP37") (pin "1") (pinfunction "1_1") (pintype "passive"))
      (node (ref "U$18") (pin "16") (pinfunction "IN-_16") (pintype "input"))
    )
    (net (code "95") (name "RX14_P") (class "Default")
      (node (ref "JP37") (pin "2") (pinfunction "2_2") (pintype "passive"))
      (node (ref "U$18") (pin "15") (pinfunction "IN+_15") (pintype "input"))
    )
    (net (code "96") (name "RX15_N") (class "Default")
      (node (ref "JP38") (pin "1") (pinfunction "1_1") (pintype "passive"))
      (node (ref "U$18") (pin "20") (pinfunction "IN-_20") (pintype "input"))
    )
    (net (code "97") (name "RX15_P") (class "Default")
      (node (ref "JP38") (pin "2") (pinfunction "2_2") (pintype "passive"))
      (node (ref "U$18") (pin "19") (pinfunction "IN+_19") (pintype "input"))
    )
    (net (code "98") (name "RX16_N") (class "Default")
      (node (ref "JP39") (pin "1") (pinfunction "1_1") (pintype "passive"))
      (node (ref "U$18") (pin "22") (pinfunction "IN-_22") (pintype "input"))
    )
    (net (code "99") (name "RX16_P") (class "Default")
      (node (ref "JP39") (pin "2") (pinfunction "2_2") (pintype "passive"))
      (node (ref "U$18") (pin "21") (pinfunction "IN+_21") (pintype "input"))
    )
    (net (code "100") (name "TX1_N") (class "Default")
      (node (ref "JP13") (pin "2") (pinfunction "2_2") (pintype "passive"))
      (node (ref "U$4") (pin "47") (pinfunction "OUT-_47") (pintype "output"))
    )
    (net (code "101") (name "TX1_P") (class "Default")
      (node (ref "JP13") (pin "1") (pinfunction "1_1") (pintype "passive"))
      (node (ref "U$4") (pin "48") (pinfunction "OUT+_48") (pintype "output"))
    )
    (net (code "102") (name "TX2_N") (class "Default")
      (node (ref "JP14") (pin "2") (pinfunction "2_2") (pintype "passive"))
      (node (ref "U$4") (pin "45") (pinfunction "OUT-_45") (pintype "output"))
    )
    (net (code "103") (name "TX2_P") (class "Default")
      (node (ref "JP14") (pin "1") (pinfunction "1_1") (pintype "passive"))
      (node (ref "U$4") (pin "46") (pinfunction "OUT+_46") (pintype "output"))
    )
    (net (code "104") (name "TX3_N") (class "Default")
      (node (ref "JP15") (pin "2") (pinfunction "2_2") (pintype "passive"))
      (node (ref "U$4") (pin "41") (pinfunction "OUT-_41") (pintype "output"))
    )
    (net (code "105") (name "TX3_P") (class "Default")
      (node (ref "JP15") (pin "1") (pinfunction "1_1") (pintype "passive"))
      (node (ref "U$4") (pin "42") (pinfunction "OUT+_42") (pintype "output"))
    )
    (net (code "106") (name "TX4_N") (class "Default")
      (node (ref "JP16") (pin "2") (pinfunction "2_2") (pintype "passive"))
      (node (ref "U$4") (pin "39") (pinfunction "OUT-_39") (pintype "output"))
    )
    (net (code "107") (name "TX4_P") (class "Default")
      (node (ref "JP16") (pin "1") (pinfunction "1_1") (pintype "passive"))
      (node (ref "U$4") (pin "40") (pinfunction "OUT+_40") (pintype "output"))
    )
    (net (code "108") (name "TX5_N") (class "Default")
      (node (ref "JP17") (pin "2") (pinfunction "2_2") (pintype "passive"))
      (node (ref "U$6") (pin "47") (pinfunction "OUT-_47") (pintype "output"))
    )
    (net (code "109") (name "TX5_P") (class "Default")
      (node (ref "JP17") (pin "1") (pinfunction "1_1") (pintype "passive"))
      (node (ref "U$6") (pin "48") (pinfunction "OUT+_48") (pintype "output"))
    )
    (net (code "110") (name "TX6_N") (class "Default")
      (node (ref "JP18") (pin "2") (pinfunction "2_2") (pintype "passive"))
      (node (ref "U$6") (pin "45") (pinfunction "OUT-_45") (pintype "output"))
    )
    (net (code "111") (name "TX6_P") (class "Default")
      (node (ref "JP18") (pin "1") (pinfunction "1_1") (pintype "passive"))
      (node (ref "U$6") (pin "46") (pinfunction "OUT+_46") (pintype "output"))
    )
    (net (code "112") (name "TX7_N") (class "Default")
      (node (ref "JP19") (pin "2") (pinfunction "2_2") (pintype "passive"))
      (node (ref "U$6") (pin "41") (pinfunction "OUT-_41") (pintype "output"))
    )
    (net (code "113") (name "TX7_P") (class "Default")
      (node (ref "JP19") (pin "1") (pinfunction "1_1") (pintype "passive"))
      (node (ref "U$6") (pin "42") (pinfunction "OUT+_42") (pintype "output"))
    )
    (net (code "114") (name "TX8_N") (class "Default")
      (node (ref "JP20") (pin "2") (pinfunction "2_2") (pintype "passive"))
      (node (ref "U$6") (pin "39") (pinfunction "OUT-_39") (pintype "output"))
    )
    (net (code "115") (name "TX8_P") (class "Default")
      (node (ref "JP20") (pin "1") (pinfunction "1_1") (pintype "passive"))
      (node (ref "U$6") (pin "40") (pinfunction "OUT+_40") (pintype "output"))
    )
    (net (code "116") (name "TX9_N") (class "Default")
      (node (ref "JP31") (pin "2") (pinfunction "2_2") (pintype "passive"))
      (node (ref "U$15") (pin "47") (pinfunction "OUT-_47") (pintype "output"))
    )
    (net (code "117") (name "TX9_P") (class "Default")
      (node (ref "JP31") (pin "1") (pinfunction "1_1") (pintype "passive"))
      (node (ref "U$15") (pin "48") (pinfunction "OUT+_48") (pintype "output"))
    )
    (net (code "118") (name "TX10_N") (class "Default")
      (node (ref "JP30") (pin "2") (pinfunction "2_2") (pintype "passive"))
      (node (ref "U$15") (pin "45") (pinfunction "OUT-_45") (pintype "output"))
    )
    (net (code "119") (name "TX10_P") (class "Default")
      (node (ref "JP30") (pin "1") (pinfunction "1_1") (pintype "passive"))
      (node (ref "U$15") (pin "46") (pinfunction "OUT+_46") (pintype "output"))
    )
    (net (code "120") (name "TX11_N") (class "Default")
      (node (ref "JP29") (pin "2") (pinfunction "2_2") (pintype "passive"))
      (node (ref "U$15") (pin "41") (pinfunction "OUT-_41") (pintype "output"))
    )
    (net (code "121") (name "TX11_P") (class "Default")
      (node (ref "JP29") (pin "1") (pinfunction "1_1") (pintype "passive"))
      (node (ref "U$15") (pin "42") (pinfunction "OUT+_42") (pintype "output"))
    )
    (net (code "122") (name "TX12_N") (class "Default")
      (node (ref "JP28") (pin "2") (pinfunction "2_2") (pintype "passive"))
      (node (ref "U$15") (pin "39") (pinfunction "OUT-_39") (pintype "output"))
    )
    (net (code "123") (name "TX12_P") (class "Default")
      (node (ref "JP28") (pin "1") (pinfunction "1_1") (pintype "passive"))
      (node (ref "U$15") (pin "40") (pinfunction "OUT+_40") (pintype "output"))
    )
    (net (code "124") (name "TX13_N") (class "Default")
      (node (ref "JP27") (pin "2") (pinfunction "2_2") (pintype "passive"))
      (node (ref "U$16") (pin "47") (pinfunction "OUT-_47") (pintype "output"))
    )
    (net (code "125") (name "TX13_P") (class "Default")
      (node (ref "JP27") (pin "1") (pinfunction "1_1") (pintype "passive"))
      (node (ref "U$16") (pin "48") (pinfunction "OUT+_48") (pintype "output"))
    )
    (net (code "126") (name "TX14_N") (class "Default")
      (node (ref "JP26") (pin "2") (pinfunction "2_2") (pintype "passive"))
      (node (ref "U$16") (pin "45") (pinfunction "OUT-_45") (pintype "output"))
    )
    (net (code "127") (name "TX14_P") (class "Default")
      (node (ref "JP26") (pin "1") (pinfunction "1_1") (pintype "passive"))
      (node (ref "U$16") (pin "46") (pinfunction "OUT+_46") (pintype "output"))
    )
    (net (code "128") (name "TX15_N") (class "Default")
      (node (ref "JP25") (pin "2") (pinfunction "2_2") (pintype "passive"))
      (node (ref "U$16") (pin "41") (pinfunction "OUT-_41") (pintype "output"))
    )
    (net (code "129") (name "TX15_P") (class "Default")
      (node (ref "JP25") (pin "1") (pinfunction "1_1") (pintype "passive"))
      (node (ref "U$16") (pin "42") (pinfunction "OUT+_42") (pintype "output"))
    )
    (net (code "130") (name "TX16_N") (class "Default")
      (node (ref "JP24") (pin "2") (pinfunction "2_2") (pintype "passive"))
      (node (ref "U$16") (pin "39") (pinfunction "OUT-_39") (pintype "output"))
    )
    (net (code "131") (name "TX16_P") (class "Default")
      (node (ref "JP24") (pin "1") (pinfunction "1_1") (pintype "passive"))
      (node (ref "U$16") (pin "40") (pinfunction "OUT+_40") (pintype "output"))
    )
    (net (code "132") (name "VCC") (class "Default")
      (node (ref "C1") (pin "1") (pinfunction "1_1") (pintype "passive"))
      (node (ref "C3") (pin "1") (pinfunction "1_1") (pintype "passive"))
      (node (ref "C4") (pin "1") (pinfunction "1_1") (pintype "passive"))
      (node (ref "U$1") (pin "51") (pinfunction "P$11_51") (pintype "bidirectional"))
      (node (ref "U$1") (pin "57") (pinfunction "P$17_57") (pintype "bidirectional"))
      (node (ref "U$1") (pin "63") (pinfunction "P$23_63") (pintype "bidirectional"))
      (node (ref "U$1") (pin "69") (pinfunction "P$29_69") (pintype "bidirectional"))
      (node (ref "U$1") (pin "75") (pinfunction "P$35_75") (pintype "bidirectional"))
      (node (ref "U$15") (pin "10") (pinfunction "VCC1_10") (pintype "bidirectional"))
      (node (ref "U$15") (pin "11") (pinfunction "VCC1_11") (pintype "bidirectional"))
      (node (ref "U$15") (pin "28") (pinfunction "VCC1_28") (pintype "bidirectional"))
      (node (ref "U$15") (pin "29") (pinfunction "VCC1_29") (pintype "bidirectional"))
      (node (ref "U$15") (pin "3") (pinfunction "VCC1_3") (pintype "bidirectional"))
      (node (ref "U$15") (pin "30") (pinfunction "VCC1_30") (pintype "bidirectional"))
      (node (ref "U$15") (pin "32") (pinfunction "VCC1_32") (pintype "bidirectional"))
      (node (ref "U$15") (pin "33") (pinfunction "VCC1_33") (pintype "bidirectional"))
      (node (ref "U$15") (pin "4") (pinfunction "VCC1_4") (pintype "bidirectional"))
      (node (ref "U$15") (pin "5") (pinfunction "VCC1_5") (pintype "bidirectional"))
      (node (ref "U$15") (pin "7") (pinfunction "VCC1_7") (pintype "bidirectional"))
      (node (ref "U$16") (pin "10") (pinfunction "VCC1_10") (pintype "bidirectional"))
      (node (ref "U$16") (pin "11") (pinfunction "VCC1_11") (pintype "bidirectional"))
      (node (ref "U$16") (pin "28") (pinfunction "VCC1_28") (pintype "bidirectional"))
      (node (ref "U$16") (pin "29") (pinfunction "VCC1_29") (pintype "bidirectional"))
      (node (ref "U$16") (pin "3") (pinfunction "VCC1_3") (pintype "bidirectional"))
      (node (ref "U$16") (pin "30") (pinfunction "VCC1_30") (pintype "bidirectional"))
      (node (ref "U$16") (pin "32") (pinfunction "VCC1_32") (pintype "bidirectional"))
      (node (ref "U$16") (pin "33") (pinfunction "VCC1_33") (pintype "bidirectional"))
      (node (ref "U$16") (pin "4") (pinfunction "VCC1_4") (pintype "bidirectional"))
      (node (ref "U$16") (pin "5") (pinfunction "VCC1_5") (pintype "bidirectional"))
      (node (ref "U$16") (pin "7") (pinfunction "VCC1_7") (pintype "bidirectional"))
      (node (ref "U$17") (pin "10") (pinfunction "VCC1_10") (pintype "bidirectional"))
      (node (ref "U$17") (pin "11") (pinfunction "VCC1_11") (pintype "bidirectional"))
      (node (ref "U$17") (pin "28") (pinfunction "VCC1_28") (pintype "bidirectional"))
      (node (ref "U$17") (pin "29") (pinfunction "VCC1_29") (pintype "bidirectional"))
      (node (ref "U$17") (pin "3") (pinfunction "VCC1_3") (pintype "bidirectional"))
      (node (ref "U$17") (pin "30") (pinfunction "VCC1_30") (pintype "bidirectional"))
      (node (ref "U$17") (pin "32") (pinfunction "VCC1_32") (pintype "bidirectional"))
      (node (ref "U$17") (pin "33") (pinfunction "VCC1_33") (pintype "bidirectional"))
      (node (ref "U$17") (pin "4") (pinfunction "VCC1_4") (pintype "bidirectional"))
      (node (ref "U$17") (pin "5") (pinfunction "VCC1_5") (pintype "bidirectional"))
      (node (ref "U$17") (pin "7") (pinfunction "VCC1_7") (pintype "bidirectional"))
      (node (ref "U$18") (pin "10") (pinfunction "VCC1_10") (pintype "bidirectional"))
      (node (ref "U$18") (pin "11") (pinfunction "VCC1_11") (pintype "bidirectional"))
      (node (ref "U$18") (pin "28") (pinfunction "VCC1_28") (pintype "bidirectional"))
      (node (ref "U$18") (pin "29") (pinfunction "VCC1_29") (pintype "bidirectional"))
      (node (ref "U$18") (pin "3") (pinfunction "VCC1_3") (pintype "bidirectional"))
      (node (ref "U$18") (pin "30") (pinfunction "VCC1_30") (pintype "bidirectional"))
      (node (ref "U$18") (pin "32") (pinfunction "VCC1_32") (pintype "bidirectional"))
      (node (ref "U$18") (pin "33") (pinfunction "VCC1_33") (pintype "bidirectional"))
      (node (ref "U$18") (pin "4") (pinfunction "VCC1_4") (pintype "bidirectional"))
      (node (ref "U$18") (pin "5") (pinfunction "VCC1_5") (pintype "bidirectional"))
      (node (ref "U$18") (pin "7") (pinfunction "VCC1_7") (pintype "bidirectional"))
      (node (ref "U$4") (pin "10") (pinfunction "VCC1_10") (pintype "bidirectional"))
      (node (ref "U$4") (pin "11") (pinfunction "VCC1_11") (pintype "bidirectional"))
      (node (ref "U$4") (pin "28") (pinfunction "VCC1_28") (pintype "bidirectional"))
      (node (ref "U$4") (pin "29") (pinfunction "VCC1_29") (pintype "bidirectional"))
      (node (ref "U$4") (pin "3") (pinfunction "VCC1_3") (pintype "bidirectional"))
      (node (ref "U$4") (pin "30") (pinfunction "VCC1_30") (pintype "bidirectional"))
      (node (ref "U$4") (pin "32") (pinfunction "VCC1_32") (pintype "bidirectional"))
      (node (ref "U$4") (pin "33") (pinfunction "VCC1_33") (pintype "bidirectional"))
      (node (ref "U$4") (pin "4") (pinfunction "VCC1_4") (pintype "bidirectional"))
      (node (ref "U$4") (pin "5") (pinfunction "VCC1_5") (pintype "bidirectional"))
      (node (ref "U$4") (pin "7") (pinfunction "VCC1_7") (pintype "bidirectional"))
      (node (ref "U$6") (pin "10") (pinfunction "VCC1_10") (pintype "bidirectional"))
      (node (ref "U$6") (pin "11") (pinfunction "VCC1_11") (pintype "bidirectional"))
      (node (ref "U$6") (pin "28") (pinfunction "VCC1_28") (pintype "bidirectional"))
      (node (ref "U$6") (pin "29") (pinfunction "VCC1_29") (pintype "bidirectional"))
      (node (ref "U$6") (pin "3") (pinfunction "VCC1_3") (pintype "bidirectional"))
      (node (ref "U$6") (pin "30") (pinfunction "VCC1_30") (pintype "bidirectional"))
      (node (ref "U$6") (pin "32") (pinfunction "VCC1_32") (pintype "bidirectional"))
      (node (ref "U$6") (pin "33") (pinfunction "VCC1_33") (pintype "bidirectional"))
      (node (ref "U$6") (pin "4") (pinfunction "VCC1_4") (pintype "bidirectional"))
      (node (ref "U$6") (pin "5") (pinfunction "VCC1_5") (pintype "bidirectional"))
      (node (ref "U$6") (pin "7") (pinfunction "VCC1_7") (pintype "bidirectional"))
      (node (ref "U$7") (pin "10") (pinfunction "VCC1_10") (pintype "bidirectional"))
      (node (ref "U$7") (pin "11") (pinfunction "VCC1_11") (pintype "bidirectional"))
      (node (ref "U$7") (pin "28") (pinfunction "VCC1_28") (pintype "bidirectional"))
      (node (ref "U$7") (pin "29") (pinfunction "VCC1_29") (pintype "bidirectional"))
      (node (ref "U$7") (pin "3") (pinfunction "VCC1_3") (pintype "bidirectional"))
      (node (ref "U$7") (pin "30") (pinfunction "VCC1_30") (pintype "bidirectional"))
      (node (ref "U$7") (pin "32") (pinfunction "VCC1_32") (pintype "bidirectional"))
      (node (ref "U$7") (pin "33") (pinfunction "VCC1_33") (pintype "bidirectional"))
      (node (ref "U$7") (pin "4") (pinfunction "VCC1_4") (pintype "bidirectional"))
      (node (ref "U$7") (pin "5") (pinfunction "VCC1_5") (pintype "bidirectional"))
      (node (ref "U$7") (pin "7") (pinfunction "VCC1_7") (pintype "bidirectional"))
      (node (ref "U$8") (pin "10") (pinfunction "VCC1_10") (pintype "bidirectional"))
      (node (ref "U$8") (pin "11") (pinfunction "VCC1_11") (pintype "bidirectional"))
      (node (ref "U$8") (pin "28") (pinfunction "VCC1_28") (pintype "bidirectional"))
      (node (ref "U$8") (pin "29") (pinfunction "VCC1_29") (pintype "bidirectional"))
      (node (ref "U$8") (pin "3") (pinfunction "VCC1_3") (pintype "bidirectional"))
      (node (ref "U$8") (pin "30") (pinfunction "VCC1_30") (pintype "bidirectional"))
      (node (ref "U$8") (pin "32") (pinfunction "VCC1_32") (pintype "bidirectional"))
      (node (ref "U$8") (pin "33") (pinfunction "VCC1_33") (pintype "bidirectional"))
      (node (ref "U$8") (pin "4") (pinfunction "VCC1_4") (pintype "bidirectional"))
      (node (ref "U$8") (pin "5") (pinfunction "VCC1_5") (pintype "bidirectional"))
      (node (ref "U$8") (pin "7") (pinfunction "VCC1_7") (pintype "bidirectional"))
    )
    (net (code "133") (name "unconnected-(U$1A-P$1-Pad1)") (class "Default")
      (node (ref "U$1") (pin "1") (pinfunction "P$1_1") (pintype "bidirectional"))
    )
    (net (code "134") (name "unconnected-(U$1A-P$2-Pad2)") (class "Default")
      (node (ref "U$1") (pin "2") (pinfunction "P$2_2") (pintype "bidirectional"))
    )
    (net (code "135") (name "unconnected-(U$1A-P$3-Pad3)") (class "Default")
      (node (ref "U$1") (pin "3") (pinfunction "P$3_3") (pintype "bidirectional"))
    )
    (net (code "136") (name "unconnected-(U$1A-P$4-Pad4)") (class "Default")
      (node (ref "U$1") (pin "4") (pinfunction "P$4_4") (pintype "bidirectional"))
    )
    (net (code "137") (name "unconnected-(U$1A-P$5-Pad5)") (class "Default")
      (node (ref "U$1") (pin "5") (pinfunction "P$5_5") (pintype "bidirectional"))
    )
    (net (code "138") (name "unconnected-(U$1A-P$6-Pad6)") (class "Default")
      (node (ref "U$1") (pin "6") (pinfunction "P$6_6") (pintype "bidirectional"))
    )
    (net (code "139") (name "unconnected-(U$1A-P$7-Pad7)") (class "Default")
      (node (ref "U$1") (pin "7") (pinfunction "P$7_7") (pintype "bidirectional"))
    )
    (net (code "140") (name "unconnected-(U$1A-P$8-Pad8)") (class "Default")
      (node (ref "U$1") (pin "8") (pinfunction "P$8_8") (pintype "bidirectional"))
    )
    (net (code "141") (name "unconnected-(U$1A-P$9-Pad9)") (class "Default")
      (node (ref "U$1") (pin "9") (pinfunction "P$9_9") (pintype "bidirectional"))
    )
    (net (code "142") (name "unconnected-(U$1A-P$10-Pad10)") (class "Default")
      (node (ref "U$1") (pin "10") (pinfunction "P$10_10") (pintype "bidirectional"))
    )
    (net (code "143") (name "unconnected-(U$1A-P$11-Pad11)") (class "Default")
      (node (ref "U$1") (pin "11") (pinfunction "P$11_11") (pintype "bidirectional"))
    )
    (net (code "144") (name "unconnected-(U$1A-P$12-Pad12)") (class "Default")
      (node (ref "U$1") (pin "12") (pinfunction "P$12_12") (pintype "bidirectional"))
    )
    (net (code "145") (name "unconnected-(U$1A-P$13-Pad13)") (class "Default")
      (node (ref "U$1") (pin "13") (pinfunction "P$13_13") (pintype "bidirectional"))
    )
    (net (code "146") (name "unconnected-(U$1A-P$14-Pad14)") (class "Default")
      (node (ref "U$1") (pin "14") (pinfunction "P$14_14") (pintype "bidirectional"))
    )
    (net (code "147") (name "unconnected-(U$1A-P$15-Pad15)") (class "Default")
      (node (ref "U$1") (pin "15") (pinfunction "P$15_15") (pintype "bidirectional"))
    )
    (net (code "148") (name "unconnected-(U$1A-P$16-Pad16)") (class "Default")
      (node (ref "U$1") (pin "16") (pinfunction "P$16_16") (pintype "bidirectional"))
    )
    (net (code "149") (name "unconnected-(U$1A-P$17-Pad17)") (class "Default")
      (node (ref "U$1") (pin "17") (pinfunction "P$17_17") (pintype "bidirectional"))
    )
    (net (code "150") (name "unconnected-(U$1A-P$18-Pad18)") (class "Default")
      (node (ref "U$1") (pin "18") (pinfunction "P$18_18") (pintype "bidirectional"))
    )
    (net (code "151") (name "unconnected-(U$1A-P$19-Pad19)") (class "Default")
      (node (ref "U$1") (pin "19") (pinfunction "P$19_19") (pintype "bidirectional"))
    )
    (net (code "152") (name "unconnected-(U$1A-P$20-Pad20)") (class "Default")
      (node (ref "U$1") (pin "20") (pinfunction "P$20_20") (pintype "bidirectional"))
    )
    (net (code "153") (name "unconnected-(U$1A-P$21-Pad21)") (class "Default")
      (node (ref "U$1") (pin "21") (pinfunction "P$21_21") (pintype "bidirectional"))
    )
    (net (code "154") (name "unconnected-(U$1A-P$22-Pad22)") (class "Default")
      (node (ref "U$1") (pin "22") (pinfunction "P$22_22") (pintype "bidirectional"))
    )
    (net (code "155") (name "unconnected-(U$1A-P$23-Pad23)") (class "Default")
      (node (ref "U$1") (pin "23") (pinfunction "P$23_23") (pintype "bidirectional"))
    )
    (net (code "156") (name "unconnected-(U$1A-P$24-Pad24)") (class "Default")
      (node (ref "U$1") (pin "24") (pinfunction "P$24_24") (pintype "bidirectional"))
    )
    (net (code "157") (name "unconnected-(U$1A-P$25-Pad25)") (class "Default")
      (node (ref "U$1") (pin "25") (pinfunction "P$25_25") (pintype "bidirectional"))
    )
    (net (code "158") (name "unconnected-(U$1A-P$26-Pad26)") (class "Default")
      (node (ref "U$1") (pin "26") (pinfunction "P$26_26") (pintype "bidirectional"))
    )
    (net (code "159") (name "unconnected-(U$1A-P$27-Pad27)") (class "Default")
      (node (ref "U$1") (pin "27") (pinfunction "P$27_27") (pintype "bidirectional"))
    )
    (net (code "160") (name "unconnected-(U$1A-P$28-Pad28)") (class "Default")
      (node (ref "U$1") (pin "28") (pinfunction "P$28_28") (pintype "bidirectional"))
    )
    (net (code "161") (name "unconnected-(U$1A-P$29-Pad29)") (class "Default")
      (node (ref "U$1") (pin "29") (pinfunction "P$29_29") (pintype "bidirectional"))
    )
    (net (code "162") (name "unconnected-(U$1A-P$30-Pad30)") (class "Default")
      (node (ref "U$1") (pin "30") (pinfunction "P$30_30") (pintype "bidirectional"))
    )
    (net (code "163") (name "unconnected-(U$1A-P$31-Pad31)") (class "Default")
      (node (ref "U$1") (pin "31") (pinfunction "P$31_31") (pintype "bidirectional"))
    )
    (net (code "164") (name "unconnected-(U$1A-P$32-Pad32)") (class "Default")
      (node (ref "U$1") (pin "32") (pinfunction "P$32_32") (pintype "bidirectional"))
    )
    (net (code "165") (name "unconnected-(U$1A-P$33-Pad33)") (class "Default")
      (node (ref "U$1") (pin "33") (pinfunction "P$33_33") (pintype "bidirectional"))
    )
    (net (code "166") (name "unconnected-(U$1A-P$34-Pad34)") (class "Default")
      (node (ref "U$1") (pin "34") (pinfunction "P$34_34") (pintype "bidirectional"))
    )
    (net (code "167") (name "unconnected-(U$1A-P$35-Pad35)") (class "Default")
      (node (ref "U$1") (pin "35") (pinfunction "P$35_35") (pintype "bidirectional"))
    )
    (net (code "168") (name "unconnected-(U$1A-P$36-Pad36)") (class "Default")
      (node (ref "U$1") (pin "36") (pinfunction "P$36_36") (pintype "bidirectional"))
    )
    (net (code "169") (name "unconnected-(U$1A-P$37-Pad37)") (class "Default")
      (node (ref "U$1") (pin "37") (pinfunction "P$37_37") (pintype "bidirectional"))
    )
    (net (code "170") (name "unconnected-(U$1A-P$38-Pad38)") (class "Default")
      (node (ref "U$1") (pin "38") (pinfunction "P$38_38") (pintype "bidirectional"))
    )
    (net (code "171") (name "unconnected-(U$1A-P$39-Pad39)") (class "Default")
      (node (ref "U$1") (pin "39") (pinfunction "P$39_39") (pintype "bidirectional"))
    )
    (net (code "172") (name "unconnected-(U$1A-P$40-Pad40)") (class "Default")
      (node (ref "U$1") (pin "40") (pinfunction "P$40_40") (pintype "bidirectional"))
    )
    (net (code "173") (name "unconnected-(U$1B-P$1-Pad41)") (class "Default")
      (node (ref "U$1") (pin "41") (pinfunction "P$1_41") (pintype "bidirectional"))
    )
    (net (code "174") (name "unconnected-(U$1B-P$2-Pad42)") (class "Default")
      (node (ref "U$1") (pin "42") (pinfunction "P$2_42") (pintype "bidirectional"))
    )
    (net (code "175") (name "unconnected-(U$1B-P$3-Pad43)") (class "Default")
      (node (ref "U$1") (pin "43") (pinfunction "P$3_43") (pintype "bidirectional"))
    )
    (net (code "176") (name "unconnected-(U$1B-P$4-Pad44)") (class "Default")
      (node (ref "U$1") (pin "44") (pinfunction "P$4_44") (pintype "bidirectional"))
    )
    (net (code "177") (name "unconnected-(U$1B-P$5-Pad45)") (class "Default")
      (node (ref "U$1") (pin "45") (pinfunction "P$5_45") (pintype "bidirectional"))
    )
    (net (code "178") (name "unconnected-(U$1B-P$6-Pad46)") (class "Default")
      (node (ref "U$1") (pin "46") (pinfunction "P$6_46") (pintype "bidirectional"))
    )
    (net (code "179") (name "unconnected-(U$1B-P$12-Pad52)") (class "Default")
      (node (ref "U$1") (pin "52") (pinfunction "P$12_52") (pintype "bidirectional"))
    )
    (net (code "180") (name "unconnected-(U$1B-P$18-Pad58)") (class "Default")
      (node (ref "U$1") (pin "58") (pinfunction "P$18_58") (pintype "bidirectional"))
    )
    (net (code "181") (name "unconnected-(U$1B-P$24-Pad64)") (class "Default")
      (node (ref "U$1") (pin "64") (pinfunction "P$24_64") (pintype "bidirectional"))
    )
    (net (code "182") (name "unconnected-(U$1B-P$30-Pad70)") (class "Default")
      (node (ref "U$1") (pin "70") (pinfunction "P$30_70") (pintype "bidirectional"))
    )
    (net (code "183") (name "unconnected-(U$1B-P$36-Pad76)") (class "Default")
      (node (ref "U$1") (pin "76") (pinfunction "P$36_76") (pintype "bidirectional"))
    )
    (net (code "184") (name "unconnected-(U$1B-P$41-Pad81)") (class "Default")
      (node (ref "U$1") (pin "81") (pinfunction "P$41_81") (pintype "bidirectional"))
    )
    (net (code "185") (name "unconnected-(U$1B-P$42-Pad82)") (class "Default")
      (node (ref "U$1") (pin "82") (pinfunction "P$42_82") (pintype "bidirectional"))
    )
    (net (code "186") (name "unconnected-(U$1B-P$47-Pad87)") (class "Default")
      (node (ref "U$1") (pin "87") (pinfunction "P$47_87") (pintype "bidirectional"))
    )
    (net (code "187") (name "unconnected-(U$1B-P$48-Pad88)") (class "Default")
      (node (ref "U$1") (pin "88") (pinfunction "P$48_88") (pintype "bidirectional"))
    )
    (net (code "188") (name "unconnected-(U$1B-P$53-Pad93)") (class "Default")
      (node (ref "U$1") (pin "93") (pinfunction "P$53_93") (pintype "bidirectional"))
    )
    (net (code "189") (name "unconnected-(U$1B-P$54-Pad94)") (class "Default")
      (node (ref "U$1") (pin "94") (pinfunction "P$54_94") (pintype "bidirectional"))
    )
    (net (code "190") (name "unconnected-(U$1B-P$55-Pad95)") (class "Default")
      (node (ref "U$1") (pin "95") (pinfunction "P$55_95") (pintype "bidirectional"))
    )
    (net (code "191") (name "unconnected-(U$1B-P$56-Pad96)") (class "Default")
      (node (ref "U$1") (pin "96") (pinfunction "P$56_96") (pintype "bidirectional"))
    )
    (net (code "192") (name "unconnected-(U$1B-P$57-Pad97)") (class "Default")
      (node (ref "U$1") (pin "97") (pinfunction "P$57_97") (pintype "bidirectional"))
    )
    (net (code "193") (name "unconnected-(U$1B-P$58-Pad98)") (class "Default")
      (node (ref "U$1") (pin "98") (pinfunction "P$58_98") (pintype "bidirectional"))
    )
    (net (code "194") (name "unconnected-(U$1B-P$59-Pad99)") (class "Default")
      (node (ref "U$1") (pin "99") (pinfunction "P$59_99") (pintype "bidirectional"))
    )
    (net (code "195") (name "unconnected-(U$1B-P$60-Pad100)") (class "Default")
      (node (ref "U$1") (pin "100") (pinfunction "P$60_100") (pintype "bidirectional"))
    )
    (net (code "196") (name "unconnected-(U$1C-P$5-Pad105)") (class "Default")
      (node (ref "U$1") (pin "105") (pinfunction "P$5_105") (pintype "bidirectional"))
    )
    (net (code "197") (name "unconnected-(U$1C-P$6-Pad106)") (class "Default")
      (node (ref "U$1") (pin "106") (pinfunction "P$6_106") (pintype "bidirectional"))
    )
    (net (code "198") (name "unconnected-(U$1C-P$11-Pad111)") (class "Default")
      (node (ref "U$1") (pin "111") (pinfunction "P$11_111") (pintype "bidirectional"))
    )
    (net (code "199") (name "unconnected-(U$1C-P$12-Pad112)") (class "Default")
      (node (ref "U$1") (pin "112") (pinfunction "P$12_112") (pintype "bidirectional"))
    )
    (net (code "200") (name "unconnected-(U$1C-P$17-Pad117)") (class "Default")
      (node (ref "U$1") (pin "117") (pinfunction "P$17_117") (pintype "bidirectional"))
    )
    (net (code "201") (name "unconnected-(U$1C-P$18-Pad118)") (class "Default")
      (node (ref "U$1") (pin "118") (pinfunction "P$18_118") (pintype "bidirectional"))
    )
    (net (code "202") (name "unconnected-(U$1C-P$23-Pad123)") (class "Default")
      (node (ref "U$1") (pin "123") (pinfunction "P$23_123") (pintype "bidirectional"))
    )
    (net (code "203") (name "unconnected-(U$1C-P$24-Pad124)") (class "Default")
      (node (ref "U$1") (pin "124") (pinfunction "P$24_124") (pintype "bidirectional"))
    )
    (net (code "204") (name "unconnected-(U$1C-P$29-Pad129)") (class "Default")
      (node (ref "U$1") (pin "129") (pinfunction "P$29_129") (pintype "bidirectional"))
    )
    (net (code "205") (name "unconnected-(U$1C-P$30-Pad130)") (class "Default")
      (node (ref "U$1") (pin "130") (pinfunction "P$30_130") (pintype "bidirectional"))
    )
    (net (code "206") (name "unconnected-(U$1C-P$35-Pad135)") (class "Default")
      (node (ref "U$1") (pin "135") (pinfunction "P$35_135") (pintype "bidirectional"))
    )
    (net (code "207") (name "unconnected-(U$1C-P$36-Pad136)") (class "Default")
      (node (ref "U$1") (pin "136") (pinfunction "P$36_136") (pintype "bidirectional"))
    )
    (net (code "208") (name "unconnected-(U$1C-P$41-Pad141)") (class "Default")
      (node (ref "U$1") (pin "141") (pinfunction "P$41_141") (pintype "bidirectional"))
    )
    (net (code "209") (name "unconnected-(U$1C-P$42-Pad142)") (class "Default")
      (node (ref "U$1") (pin "142") (pinfunction "P$42_142") (pintype "bidirectional"))
    )
    (net (code "210") (name "unconnected-(U$1C-P$47-Pad147)") (class "Default")
      (node (ref "U$1") (pin "147") (pinfunction "P$47_147") (pintype "bidirectional"))
    )
    (net (code "211") (name "unconnected-(U$1C-P$48-Pad148)") (class "Default")
      (node (ref "U$1") (pin "148") (pinfunction "P$48_148") (pintype "bidirectional"))
    )
    (net (code "212") (name "unconnected-(U$1C-P$49-Pad149)") (class "Default")
      (node (ref "U$1") (pin "149") (pinfunction "P$49_149") (pintype "bidirectional"))
    )
    (net (code "213") (name "unconnected-(U$1C-P$50-Pad150)") (class "Default")
      (node (ref "U$1") (pin "150") (pinfunction "P$50_150") (pintype "bidirectional"))
    )
    (net (code "214") (name "unconnected-(U$1C-P$52-Pad152)") (class "Default")
      (node (ref "U$1") (pin "152") (pinfunction "P$52_152") (pintype "bidirectional"))
    )
    (net (code "215") (name "unconnected-(U$1C-P$54-Pad154)") (class "Default")
      (node (ref "U$1") (pin "154") (pinfunction "P$54_154") (pintype "bidirectional"))
    )
    (net (code "216") (name "unconnected-(U$1C-P$55-Pad155)") (class "Default")
      (node (ref "U$1") (pin "155") (pinfunction "P$55_155") (pintype "bidirectional"))
    )
    (net (code "217") (name "unconnected-(U$1C-P$56-Pad156)") (class "Default")
      (node (ref "U$1") (pin "156") (pinfunction "P$56_156") (pintype "bidirectional"))
    )
    (net (code "218") (name "unconnected-(U$1C-P$57-Pad157)") (class "Default")
      (node (ref "U$1") (pin "157") (pinfunction "P$57_157") (pintype "bidirectional"))
    )
    (net (code "219") (name "unconnected-(U$1C-P$58-Pad158)") (class "Default")
      (node (ref "U$1") (pin "158") (pinfunction "P$58_158") (pintype "bidirectional"))
    )
    (net (code "220") (name "unconnected-(U$1C-P$59-Pad159)") (class "Default")
      (node (ref "U$1") (pin "159") (pinfunction "P$59_159") (pintype "bidirectional"))
    )
    (net (code "221") (name "unconnected-(U$1C-P$60-Pad160)") (class "Default")
      (node (ref "U$1") (pin "160") (pinfunction "P$60_160") (pintype "bidirectional"))
    )
  )
)
